# Funktionsgenerator_Power_Supply.net
KiCad netlist of a schematic drawn in EAGLE
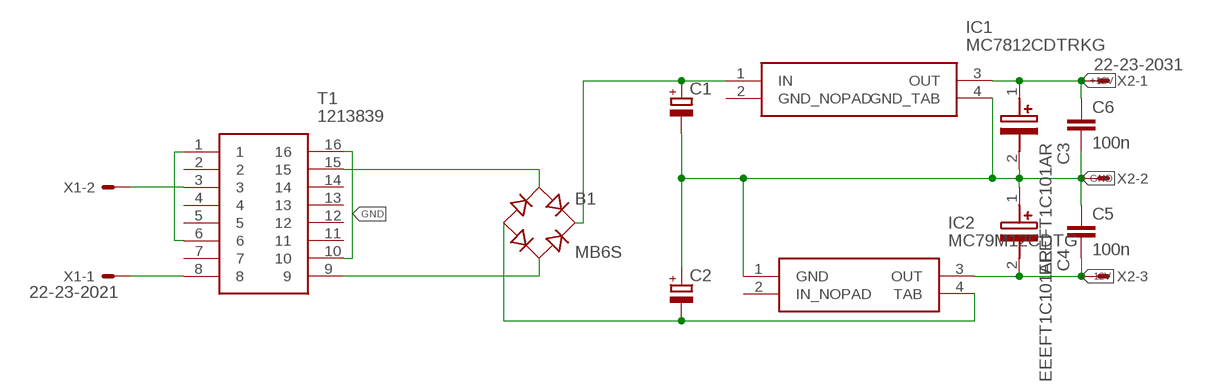
[diagram p0: schematic, sheet 1]

(export (version "E")
  (design (tool "Eeschema 10.0.6"))
  (components
    (comp (ref "B1")
      (value "MB6S")
      (footprint "eagle-import:SOIC-4")
      (libsource (lib "eagle-import") (part "MBS6"))
    )
    (comp (ref "C1")
      (value "CPOL-EUE5-13")
      (footprint "eagle-import:E5-13")
      (libsource (lib "eagle-import") (part "CPOL-EUE5-13"))
    )
    (comp (ref "C2")
      (value "CPOL-EUE5-13")
      (footprint "eagle-import:E5-13")
      (libsource (lib "eagle-import") (part "CPOL-EUE5-13"))
    )
    (comp (ref "C3")
      (value "EEEFT1C101AR")
      (footprint "eagle-import:HBV(C)")
      (fields (field (name "RS_PART_NUMBER") "7472499P"))
      (libsource (lib "eagle-import") (part "EEEFT1C101AR"))
    )
    (comp (ref "C4")
      (value "EEEFT1C101AR")
      (footprint "eagle-import:HBV(C)")
      (fields (field (name "RS_PART_NUMBER") "7472499P"))
      (libsource (lib "eagle-import") (part "EEEFT1C101AR"))
    )
    (comp (ref "C5")
      (value "100n")
      (footprint "eagle-import:C0603")
      (libsource (lib "eagle-import") (part "C-EUC0603"))
    )
    (comp (ref "C6")
      (value "100n")
      (footprint "eagle-import:C0603")
      (libsource (lib "eagle-import") (part "C-EUC0603"))
    )
    (comp (ref "IC1")
      (value "MC7812CDTRKG")
      (footprint "eagle-import:TO229P990X238-4N")
      (fields (field (name "RS_PART_NUMBER") "6889250P"))
      (libsource (lib "eagle-import") (part "MC7812CDTRKG"))
    )
    (comp (ref "IC2")
      (value "MC79M12CDTG")
      (footprint "eagle-import:TO229P990X238-4N")
      (fields (field (name "RS_PART_NUMBER") "6889326P"))
      (libsource (lib "eagle-import") (part "MC79M12CDTG"))
    )
    (comp (ref "T1")
      (value "1213839")
      (footprint "eagle-import:DIPS3500W80P500L4400H2300Q16N")
      (libsource (lib "eagle-import") (part "1213839"))
    )
    (comp (ref "X1")
      (value "22-23-2021")
      (footprint "eagle-import:22-23-2021")
      (fields (field (name "MF") "MOLEX"))
      (libsource (lib "eagle-import") (part "22-23-2021"))
    )
    (comp (ref "X2")
      (value "22-23-2031")
      (footprint "eagle-import:22-23-2031")
      (fields (field (name "MF") "MOLEX"))
      (libsource (lib "eagle-import") (part "22-23-2031"))
    )
  )
  (nets
    (net (code "1") (name "+12V") (class "Default")
      (node (ref "C3") (pin "1") (pinfunction "+_1") (pintype "bidirectional"))
      (node (ref "C6") (pin "1") (pinfunction "1_1") (pintype "passive"))
      (node (ref "IC1") (pin "3") (pinfunction "OUT_3") (pintype "output"))
      (node (ref "X2") (pin "1") (pinfunction "S_1") (pintype "passive"))
    )
    (net (code "2") (name "-12V") (class "Default")
      (node (ref "C4") (pin "2") (pinfunction "-_2") (pintype "bidirectional"))
      (node (ref "C5") (pin "2") (pinfunction "2_2") (pintype "passive"))
      (node (ref "IC2") (pin "3") (pinfunction "OUT_3") (pintype "output"))
      (node (ref "X2") (pin "3") (pinfunction "S_3") (pintype "passive"))
    )
    (net (code "3") (name "/GND_NOPAD") (class "Default")
      (node (ref "IC1") (pin "2") (pinfunction "GND_NOPAD_2") (pintype "power_in"))
    )
    (net (code "4") (name "GND") (class "Default")
      (node (ref "C1") (pin "-") (pinfunction "-_-") (pintype "passive"))
      (node (ref "C2") (pin "+") (pinfunction "+_+") (pintype "passive"))
      (node (ref "C3") (pin "2") (pinfunction "-_2") (pintype "bidirectional"))
      (node (ref "C4") (pin "1") (pinfunction "+_1") (pintype "bidirectional"))
      (node (ref "C5") (pin "1") (pinfunction "1_1") (pintype "passive"))
      (node (ref "C6") (pin "2") (pinfunction "2_2") (pintype "passive"))
      (node (ref "IC1") (pin "4") (pinfunction "GND_TAB_4") (pintype "power_in"))
      (node (ref "IC2") (pin "1") (pinfunction "GND_1") (pintype "power_in"))
      (node (ref "T1") (pin "10") (pinfunction "10_10") (pintype "bidirectional"))
      (node (ref "T1") (pin "16") (pinfunction "16_16") (pintype "bidirectional"))
      (node (ref "X2") (pin "2") (pinfunction "S_2") (pintype "passive"))
    )
    (net (code "5") (name "Net-(B1-AC1)") (class "Default")
      (node (ref "B1") (pin "~1") (pinfunction "AC1_~1") (pintype "passive"))
      (node (ref "T1") (pin "15") (pinfunction "15_15") (pintype "bidirectional"))
    )
    (net (code "6") (name "Net-(B1-AC2)") (class "Default")
      (node (ref "B1") (pin "~2") (pinfunction "AC2_~2") (pintype "passive"))
      (node (ref "T1") (pin "9") (pinfunction "9_9") (pintype "bidirectional"))
    )
    (net (code "7") (name "Net-(IC1-IN)") (class "Default")
      (node (ref "B1") (pin "+") (pinfunction "+_+") (pintype "passive"))
      (node (ref "C1") (pin "+") (pinfunction "+_+") (pintype "passive"))
      (node (ref "IC1") (pin "1") (pinfunction "IN_1") (pintype "input"))
    )
    (net (code "8") (name "Net-(IC2-TAB)") (class "Default")
      (node (ref "B1") (pin "-") (pinfunction "-_-") (pintype "passive"))
      (node (ref "C2") (pin "-") (pinfunction "-_-") (pintype "passive"))
      (node (ref "IC2") (pin "4") (pinfunction "TAB_4") (pintype "bidirectional"))
    )
    (net (code "9") (name "Net-(T1-Pad1)") (class "Default")
      (node (ref "T1") (pin "1") (pinfunction "1_1") (pintype "bidirectional"))
      (node (ref "T1") (pin "6") (pinfunction "6_6") (pintype "bidirectional"))
    )
    (net (code "10") (name "Net-(X1A-S)") (class "Default")
      (node (ref "T1") (pin "8") (pinfunction "8_8") (pintype "bidirectional"))
      (node (ref "X1") (pin "1") (pinfunction "S_1") (pintype "passive"))
    )
    (net (code "11") (name "Net-(X1B-S)") (class "Default")
      (node (ref "T1") (pin "3") (pinfunction "3_3") (pintype "bidirectional"))
      (node (ref "X1") (pin "2") (pinfunction "S_2") (pintype "passive"))
    )
    (net (code "12") (name "unconnected-(IC2-IN_NOPAD-Pad2)") (class "Default")
      (node (ref "IC2") (pin "2") (pinfunction "IN_NOPAD_2") (pintype "input"))
    )
    (net (code "13") (name "unconnected-(T1-Pad2)") (class "Default")
      (node (ref "T1") (pin "2") (pinfunction "2_2") (pintype "bidirectional"))
    )
    (net (code "14") (name "unconnected-(T1-Pad4)") (class "Default")
      (node (ref "T1") (pin "4") (pinfunction "4_4") (pintype "bidirectional"))
    )
    (net (code "15") (name "unconnected-(T1-Pad5)") (class "Default")
      (node (ref "T1") (pin "5") (pinfunction "5_5") (pintype "bidirectional"))
    )
    (net (code "16") (name "unconnected-(T1-Pad7)") (class "Default")
      (node (ref "T1") (pin "7") (pinfunction "7_7") (pintype "bidirectional"))
    )
    (net (code "17") (name "unconnected-(T1-Pad11)") (class "Default")
      (node (ref "T1") (pin "11") (pinfunction "11_11") (pintype "bidirectional"))
    )
    (net (code "18") (name "unconnected-(T1-Pad12)") (class "Default")
      (node (ref "T1") (pin "12") (pinfunction "12_12") (pintype "bidirectional"))
    )
    (net (code "19") (name "unconnected-(T1-Pad13)") (class "Default")
      (node (ref "T1") (pin "13") (pinfunction "13_13") (pintype "bidirectional"))
    )
    (net (code "20") (name "unconnected-(T1-Pad14)") (class "Default")
      (node (ref "T1") (pin "14") (pinfunction "14_14") (pintype "bidirectional"))
    )
  )
)
